# HDC1080-Breakout_v10.net
KiCad netlist of a schematic drawn in EAGLE
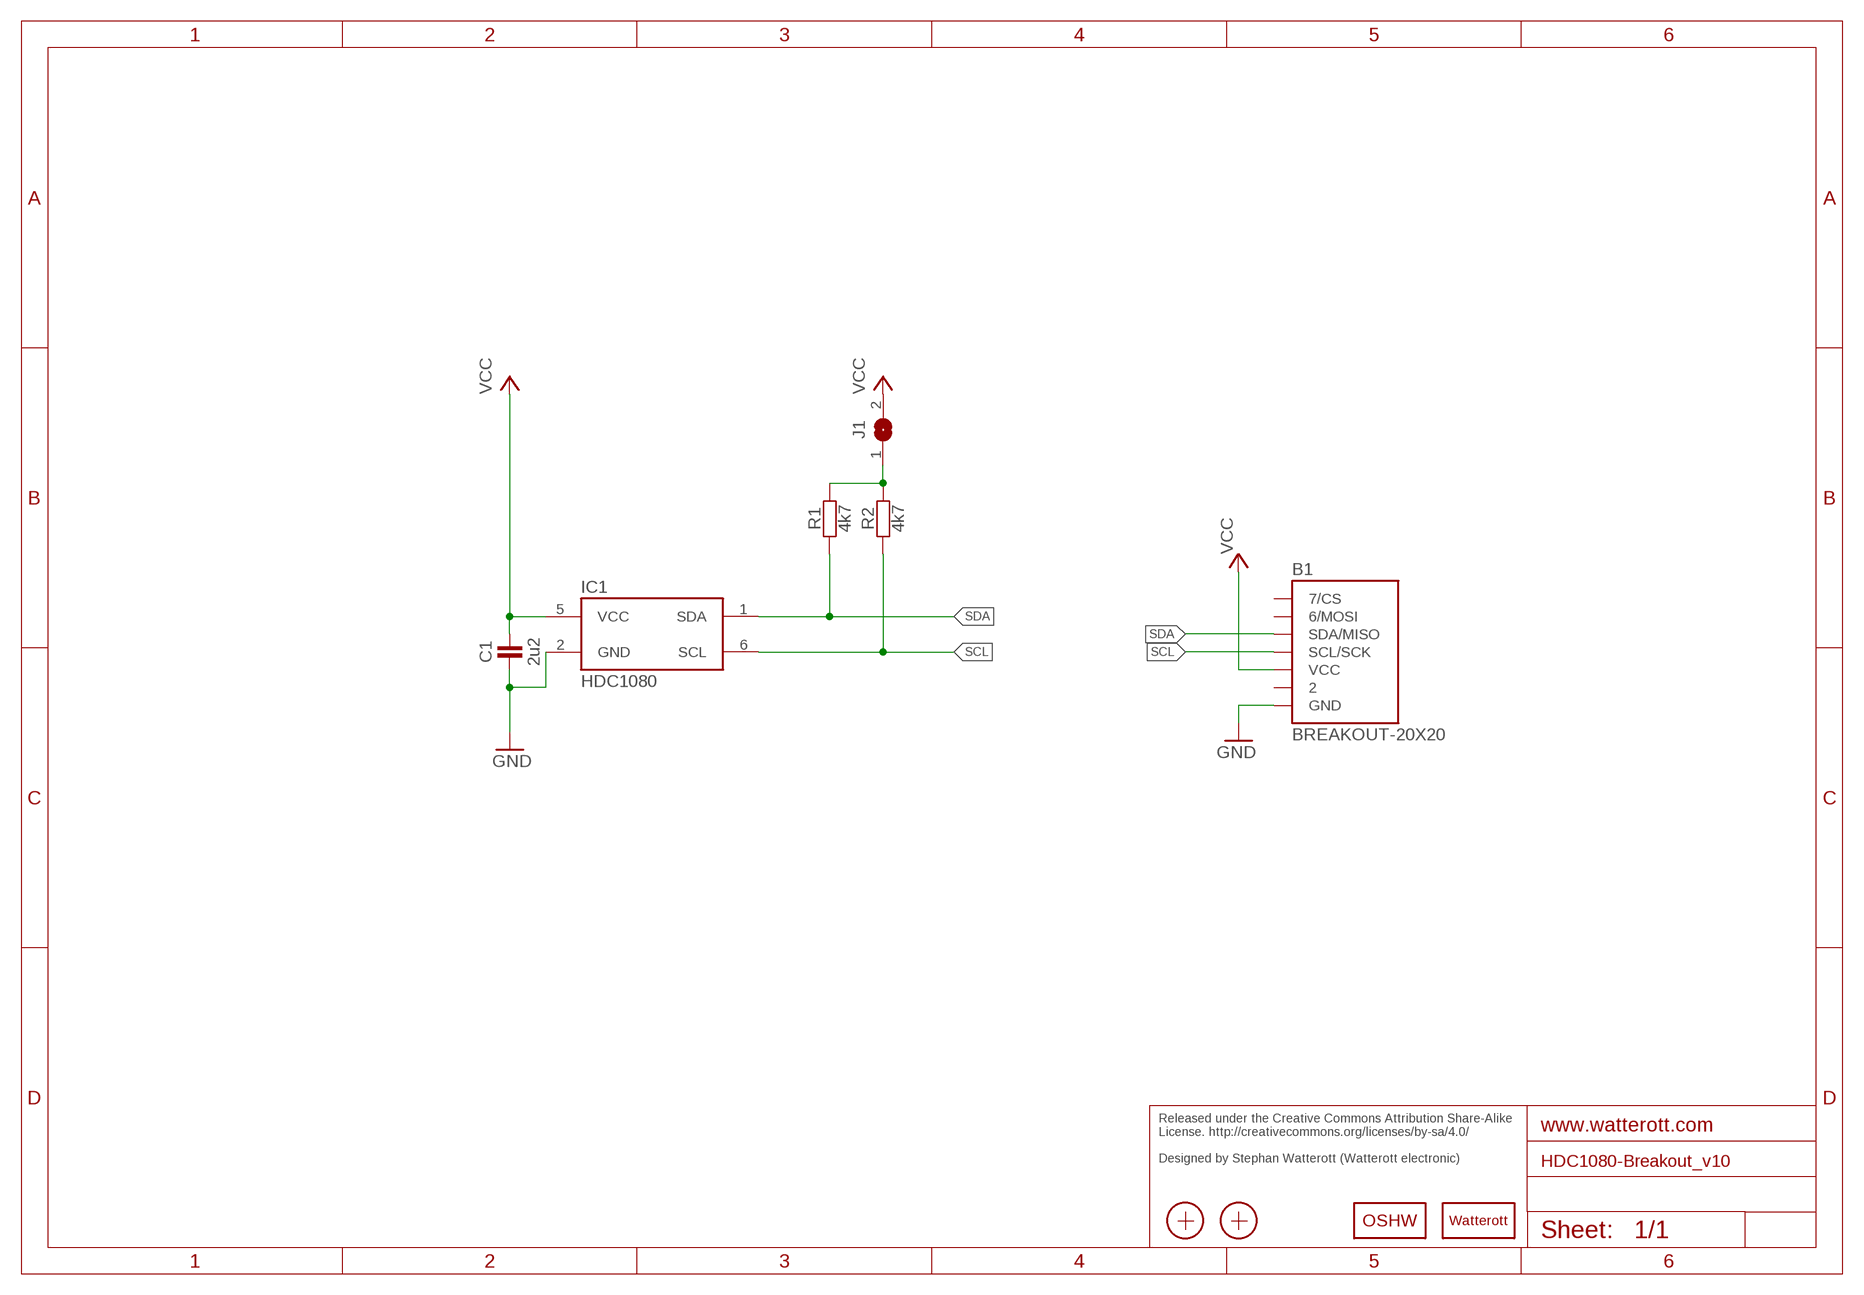
[diagram p0: schematic, sheet 1]

(export (version "E")
  (design (tool "Eeschema 10.0.6"))
  (components
    (comp (ref "B1")
      (value "BREAKOUT-20X20")
      (footprint "eagle-import:BREAKOUT-20X20")
      (libsource (lib "eagle-import") (part "BREAKOUT-20X20"))
    )
    (comp (ref "C1")
      (value "2u2")
      (footprint "eagle-import:R0402")
      (libsource (lib "eagle-import") (part "CAPACITOR-C0402"))
    )
    (comp (ref "IC1")
      (value "HDC1080")
      (footprint "eagle-import:WSON6")
      (libsource (lib "eagle-import") (part "HDC1080"))
    )
    (comp (ref "J1")
      (value "JUMPER2-0603")
      (footprint "eagle-import:JUMPER2-0603")
      (libsource (lib "eagle-import") (part "JUMPER2-0603"))
    )
    (comp (ref "LOGO2")
      (value "OSHW_LOGOX0070")
      (footprint "eagle-import:OSHW_6X70")
      (libsource (lib "eagle-import") (part "OSHW_LOGOX0070"))
    )
    (comp (ref "LOGO3")
      (value "LOGO-S_PLACE_M")
      (footprint "eagle-import:SPARK_TPLACE_M")
      (libsource (lib "eagle-import") (part "LOGO-S_PLACE_M"))
    )
    (comp (ref "R1")
      (value "4k7")
      (footprint "eagle-import:R0402")
      (libsource (lib "eagle-import") (part "RESISTOR-R0402"))
    )
    (comp (ref "R2")
      (value "4k7")
      (footprint "eagle-import:R0402")
      (libsource (lib "eagle-import") (part "RESISTOR-R0402"))
    )
    (comp (ref "X1")
      (value "PASSER-07")
      (footprint "eagle-import:PASSER_07MM")
      (libsource (lib "eagle-import") (part "PASSER-07"))
    )
    (comp (ref "X2")
      (value "PASSER-07")
      (footprint "eagle-import:PASSER_07MM")
      (libsource (lib "eagle-import") (part "PASSER-07"))
    )
  )
  (nets
    (net (code "1") (name "GND") (class "Default")
      (node (ref "B1") (pin "GND") (pinfunction "GND_GND") (pintype "power_in"))
      (node (ref "C1") (pin "1") (pinfunction "1_1") (pintype "passive"))
      (node (ref "IC1") (pin "2") (pinfunction "GND_2") (pintype "power_in"))
    )
    (net (code "2") (name "Net-(J1-Pad1)") (class "Default")
      (node (ref "J1") (pin "1") (pinfunction "1_1") (pintype "passive"))
      (node (ref "R1") (pin "2") (pinfunction "2_2") (pintype "passive"))
      (node (ref "R2") (pin "2") (pinfunction "2_2") (pintype "passive"))
    )
    (net (code "3") (name "SCL") (class "Default")
      (node (ref "B1") (pin "SCL/SCK") (pinfunction "SCL/SCK_SCL/SCK") (pintype "bidirectional"))
      (node (ref "IC1") (pin "6") (pinfunction "SCL_6") (pintype "bidirectional"))
      (node (ref "R2") (pin "1") (pinfunction "1_1") (pintype "passive"))
    )
    (net (code "4") (name "SDA") (class "Default")
      (node (ref "B1") (pin "SDA/MISO") (pinfunction "SDA/MISO_SDA/MISO") (pintype "bidirectional"))
      (node (ref "IC1") (pin "1") (pinfunction "SDA_1") (pintype "bidirectional"))
      (node (ref "R1") (pin "1") (pinfunction "1_1") (pintype "passive"))
    )
    (net (code "5") (name "VCC") (class "Default")
      (node (ref "B1") (pin "VCC") (pinfunction "VCC_VCC") (pintype "power_in"))
      (node (ref "C1") (pin "2") (pinfunction "2_2") (pintype "passive"))
      (node (ref "IC1") (pin "5") (pinfunction "VCC_5") (pintype "power_in"))
      (node (ref "J1") (pin "2") (pinfunction "2_2") (pintype "passive"))
    )
    (net (code "6") (name "unconnected-(B1-6{slash}MOSI-PadMOSI)") (class "Default")
      (node (ref "B1") (pin "MOSI") (pinfunction "6/MOSI_MOSI") (pintype "bidirectional"))
    )
    (net (code "7") (name "unconnected-(B1-7{slash}CS-PadCS)") (class "Default")
      (node (ref "B1") (pin "CS") (pinfunction "7/CS_CS") (pintype "bidirectional"))
    )
    (net (code "8") (name "unconnected-(B1-Pad2)") (class "Default")
      (node (ref "B1") (pin "2") (pinfunction "2_2") (pintype "bidirectional"))
    )
  )
)
